# POSCON_PCB.net
KiCad netlist of a schematic drawn in EAGLE
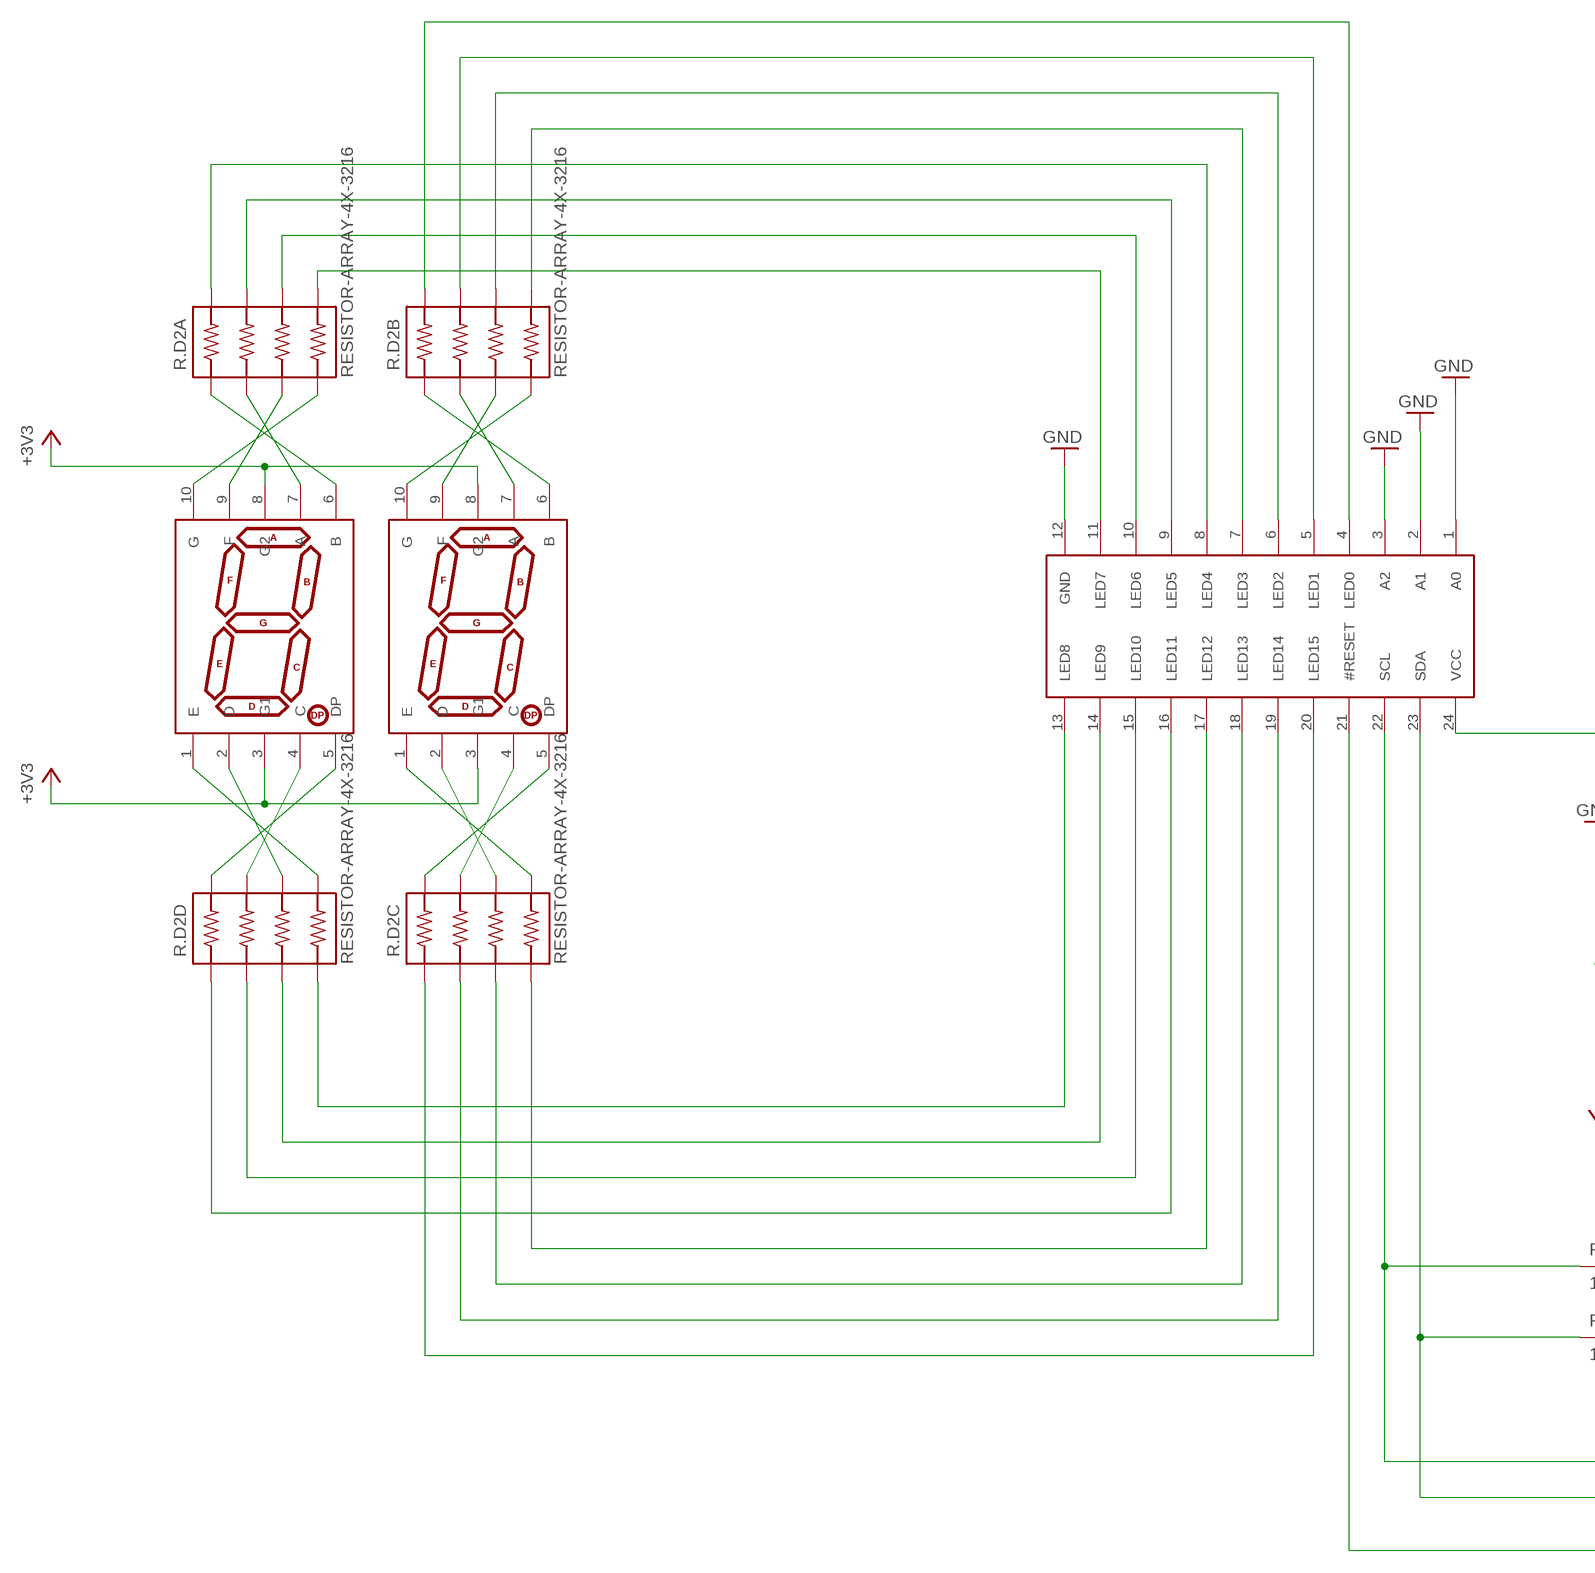
[diagram p0: schematic, sheet 1, part 1 of 2]
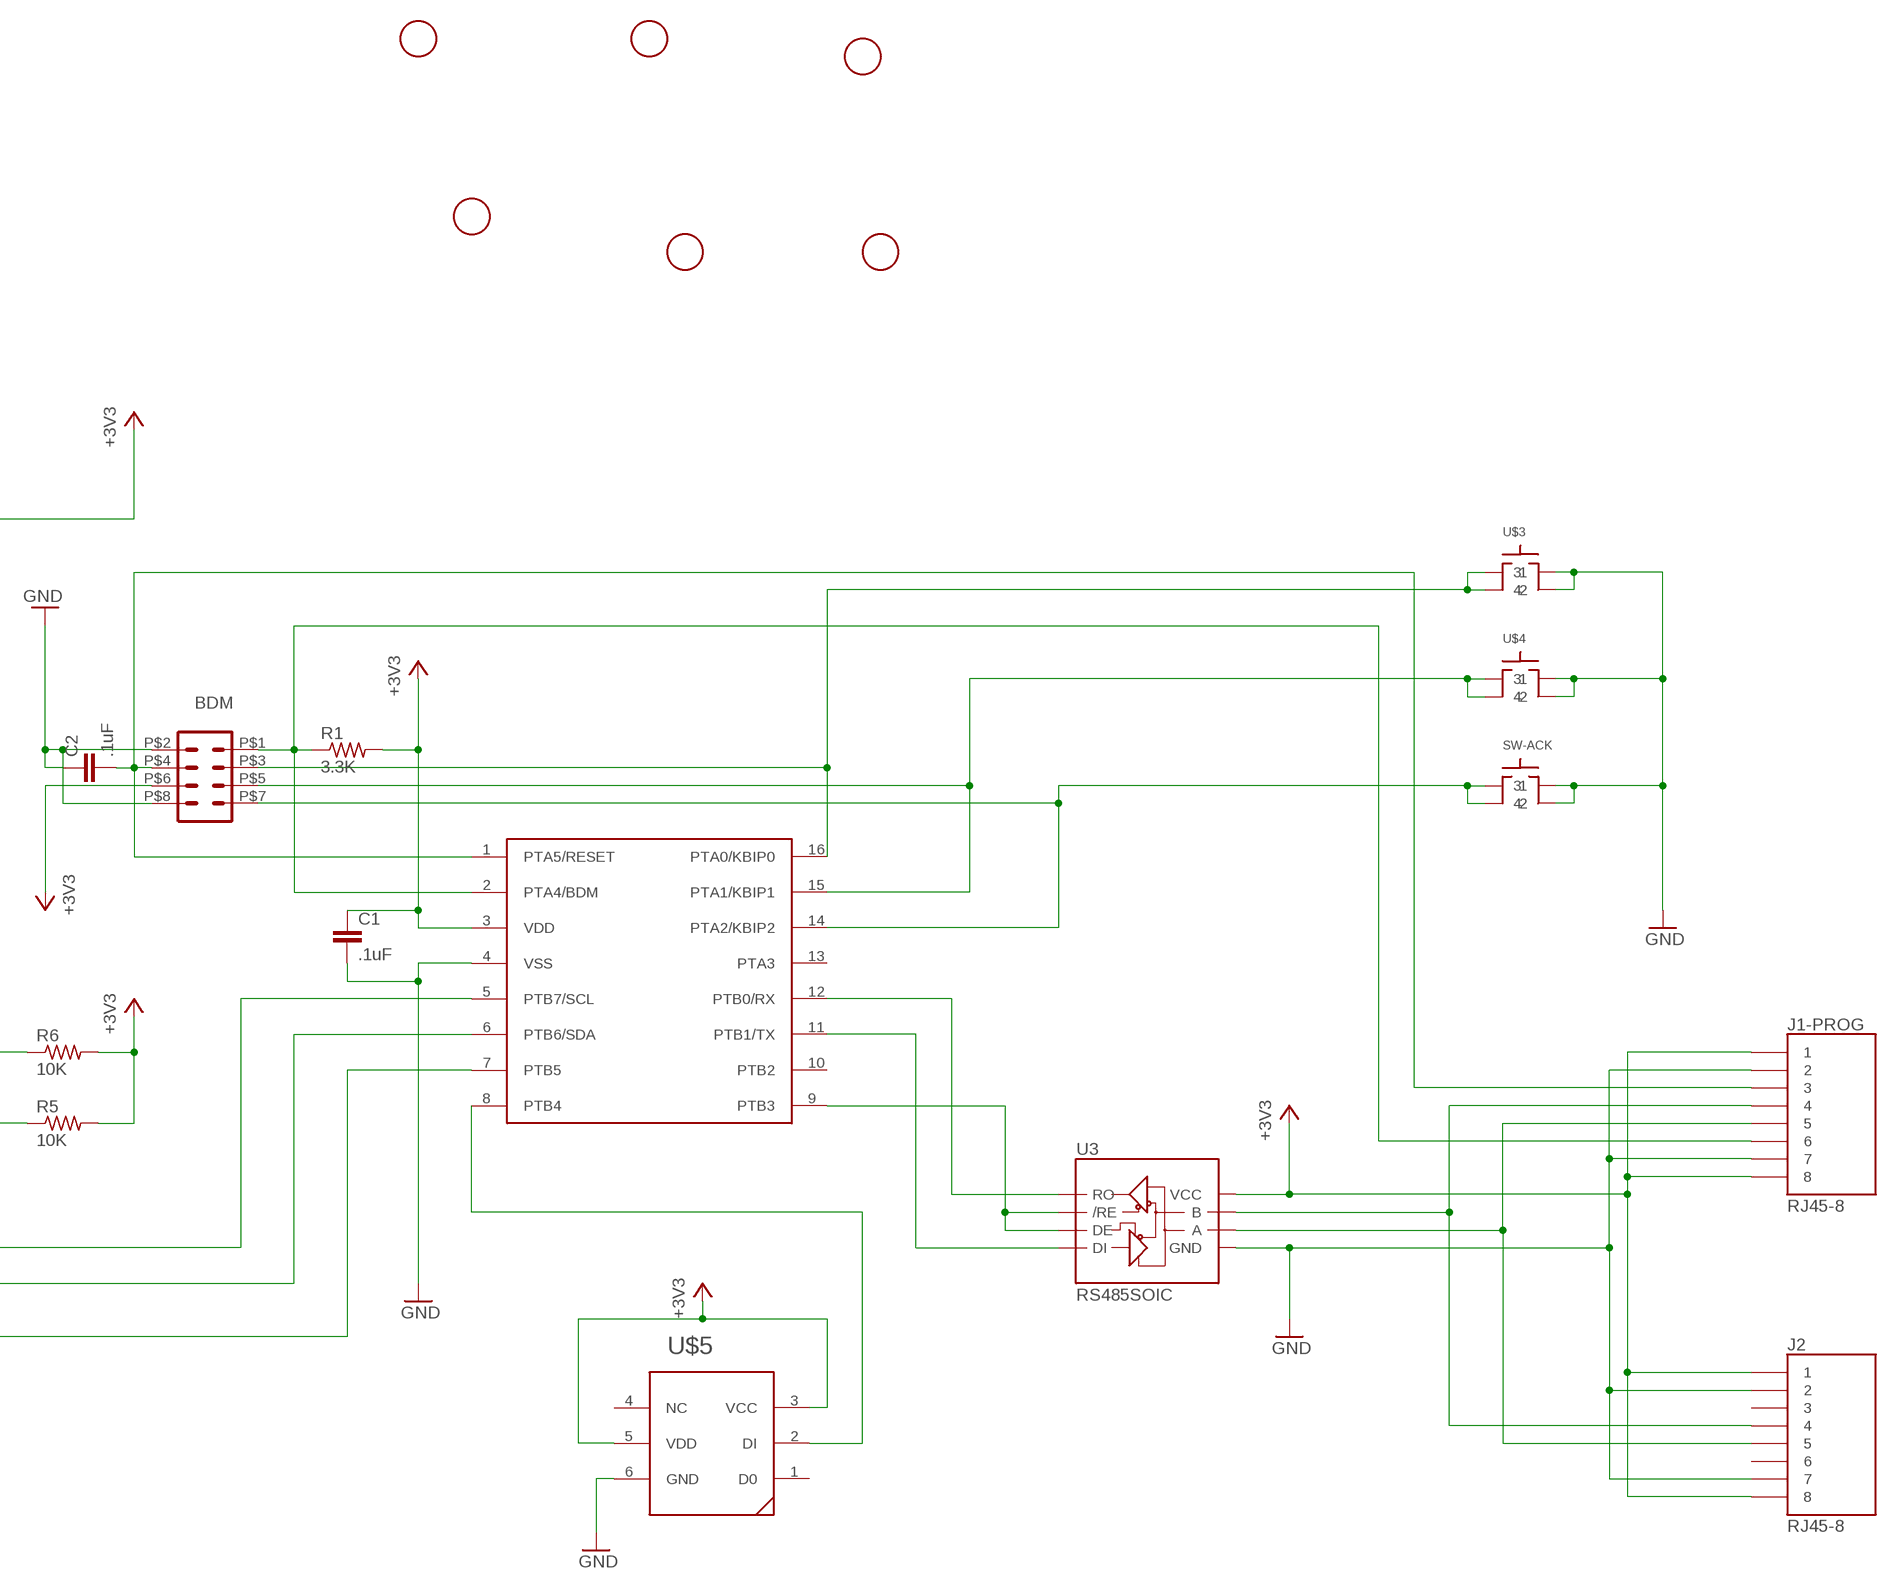
[diagram p1: schematic, sheet 1, part 2 of 2]

(export (version "E")
  (design (tool "Eeschema 10.0.6"))
  (components
    (comp (ref "BDM")
      (value "TP2X4SMD")
      (footprint "eagle-import:SMD4X2")
      (libsource (lib "eagle-import") (part "TP2X4SMD"))
    )
    (comp (ref "C1")
      (value ".1uF")
      (footprint "eagle-import:C0402")
      (libsource (lib "eagle-import") (part "RF-C0402"))
    )
    (comp (ref "C2")
      (value ".1uF")
      (footprint "eagle-import:C0402")
      (libsource (lib "eagle-import") (part "RF-C0402"))
    )
    (comp (ref "J1-PROG")
      (value "RJ45-8")
      (footprint "eagle-import:MOLEX-0955016649")
      (libsource (lib "eagle-import") (part "RJ45-8"))
    )
    (comp (ref "J2")
      (value "RJ45-8")
      (footprint "eagle-import:MOLEX-0955016649")
      (libsource (lib "eagle-import") (part "RJ45-8"))
    )
    (comp (ref "LED1")
      (value "7SEGMENT-1DIGITSMD")
      (footprint "eagle-import:7SEGMENT-1DIG-.40-SMD")
      (libsource (lib "eagle-import") (part "7SEGMENT-1DIGITSMD"))
    )
    (comp (ref "LED2")
      (value "7SEGMENT-1DIGITSMD")
      (footprint "eagle-import:7SEGMENT-1DIG-.40-SMD")
      (libsource (lib "eagle-import") (part "7SEGMENT-1DIGITSMD"))
    )
    (comp (ref "R.D2A")
      (value "RESISTOR-ARRAY-4X-3216")
      (footprint "eagle-import:3216-4X")
      (libsource (lib "eagle-import") (part "RESISTOR-ARRAY-4X-3216"))
    )
    (comp (ref "R.D2B")
      (value "RESISTOR-ARRAY-4X-3216")
      (footprint "eagle-import:3216-4X")
      (libsource (lib "eagle-import") (part "RESISTOR-ARRAY-4X-3216"))
    )
    (comp (ref "R.D2C")
      (value "RESISTOR-ARRAY-4X-3216")
      (footprint "eagle-import:3216-4X")
      (libsource (lib "eagle-import") (part "RESISTOR-ARRAY-4X-3216"))
    )
    (comp (ref "R.D2D")
      (value "RESISTOR-ARRAY-4X-3216")
      (footprint "eagle-import:3216-4X")
      (libsource (lib "eagle-import") (part "RESISTOR-ARRAY-4X-3216"))
    )
    (comp (ref "R1")
      (value "3.3K")
      (footprint "eagle-import:RF-R0402")
      (libsource (lib "eagle-import") (part "RF-R0402"))
    )
    (comp (ref "R5")
      (value "10K")
      (footprint "eagle-import:RF-R0402")
      (libsource (lib "eagle-import") (part "RF-R0402"))
    )
    (comp (ref "R6")
      (value "10K")
      (footprint "eagle-import:RF-R0402")
      (libsource (lib "eagle-import") (part "RF-R0402"))
    )
    (comp (ref "SW-ACK")
      (value "SWITCH-TACTILE-320.01E11WHT")
      (footprint "eagle-import:SWITCH-TACTILE-320.01E11WHT")
      (fields (field (name "MFGP") "320.01E11WHT"))
      (libsource (lib "eagle-import") (part "SWITCH-TACTILE-320.01E11WHT"))
    )
    (comp (ref "U$1")
      (value "FIDUCIAL")
      (footprint "eagle-import:FIDUCIAL_1MM")
      (libsource (lib "eagle-import") (part "FIDUCIAL"))
    )
    (comp (ref "U$2")
      (value "FIDUCIAL")
      (footprint "eagle-import:FIDUCIAL_1MM")
      (libsource (lib "eagle-import") (part "FIDUCIAL"))
    )
    (comp (ref "U$3")
      (value "SWITCH-TACTILE")
      (footprint "eagle-import:ESWITCH-TL3301PF")
      (libsource (lib "eagle-import") (part "SWITCH-TACTILE"))
    )
    (comp (ref "U$4")
      (value "SWITCH-TACTILE")
      (footprint "eagle-import:ESWITCH-TL3301PF")
      (libsource (lib "eagle-import") (part "SWITCH-TACTILE"))
    )
    (comp (ref "U$5")
      (value "WS2812")
      (footprint "eagle-import:PLCC-6")
      (libsource (lib "eagle-import") (part "WS2812"))
    )
    (comp (ref "U$6")
      (value "FIDUCIAL")
      (footprint "eagle-import:FIDUCIAL_1MM")
      (libsource (lib "eagle-import") (part "FIDUCIAL"))
    )
    (comp (ref "U$7")
      (value "FIDUCIAL")
      (footprint "eagle-import:FIDUCIAL_1MM")
      (libsource (lib "eagle-import") (part "FIDUCIAL"))
    )
    (comp (ref "U$8")
      (value "FIDUCIAL")
      (footprint "eagle-import:FIDUCIAL_1MM")
      (libsource (lib "eagle-import") (part "FIDUCIAL"))
    )
    (comp (ref "U$9")
      (value "FIDUCIAL")
      (footprint "eagle-import:FIDUCIAL_1MM")
      (libsource (lib "eagle-import") (part "FIDUCIAL"))
    )
    (comp (ref "U1")
      (value "MC9S08QG-DT")
      (footprint "eagle-import:TSSOP16")
      (libsource (lib "eagle-import") (part "MC9S08QG-DT"))
    )
    (comp (ref "U3")
      (value "RS485SOIC")
      (footprint "eagle-import:SO08")
      (libsource (lib "eagle-import") (part "RS485SOIC"))
    )
    (comp (ref "U4")
      (value "PCA9552")
      (footprint "eagle-import:TSSOP24")
      (fields (field (name "MFGP") "PCA9552PW,112"))
      (libsource (lib "eagle-import") (part "PCA9552"))
    )
  )
  (nets
    (net (code "1") (name "+3V3") (class "Default")
      (node (ref "BDM") (pin "P$6") (pinfunction "6_P$6") (pintype "passive"))
      (node (ref "C1") (pin "1") (pinfunction "1_1") (pintype "passive"))
      (node (ref "J1-PROG") (pin "P$1") (pinfunction "1_P$1") (pintype "bidirectional"))
      (node (ref "J1-PROG") (pin "P$8") (pinfunction "8_P$8") (pintype "bidirectional"))
      (node (ref "J2") (pin "P$1") (pinfunction "1_P$1") (pintype "bidirectional"))
      (node (ref "J2") (pin "P$8") (pinfunction "8_P$8") (pintype "bidirectional"))
      (node (ref "LED1") (pin "3") (pinfunction "G1_3") (pintype "bidirectional"))
      (node (ref "LED1") (pin "8") (pinfunction "G2_8") (pintype "bidirectional"))
      (node (ref "LED2") (pin "3") (pinfunction "G1_3") (pintype "bidirectional"))
      (node (ref "LED2") (pin "8") (pinfunction "G2_8") (pintype "bidirectional"))
      (node (ref "R1") (pin "2") (pinfunction "2_2") (pintype "passive"))
      (node (ref "R5") (pin "2") (pinfunction "2_2") (pintype "passive"))
      (node (ref "R6") (pin "2") (pinfunction "2_2") (pintype "passive"))
      (node (ref "U$5") (pin "3") (pinfunction "VCC_3") (pintype "bidirectional"))
      (node (ref "U$5") (pin "5") (pinfunction "VDD_5") (pintype "bidirectional"))
      (node (ref "U1") (pin "3") (pinfunction "VDD_3") (pintype "bidirectional"))
      (node (ref "U3") (pin "8") (pinfunction "VCC_8") (pintype "bidirectional"))
      (node (ref "U4") (pin "24") (pinfunction "VCC_24") (pintype "bidirectional"))
    )
    (net (code "2") (name "GND") (class "Default")
      (node (ref "BDM") (pin "P$2") (pinfunction "2_P$2") (pintype "passive"))
      (node (ref "BDM") (pin "P$8") (pinfunction "8_P$8") (pintype "passive"))
      (node (ref "C1") (pin "2") (pinfunction "2_2") (pintype "passive"))
      (node (ref "C2") (pin "1") (pinfunction "1_1") (pintype "passive"))
      (node (ref "J1-PROG") (pin "P$2") (pinfunction "2_P$2") (pintype "bidirectional"))
      (node (ref "J1-PROG") (pin "P$7") (pinfunction "7_P$7") (pintype "bidirectional"))
      (node (ref "J2") (pin "P$2") (pinfunction "2_P$2") (pintype "bidirectional"))
      (node (ref "J2") (pin "P$7") (pinfunction "7_P$7") (pintype "bidirectional"))
      (node (ref "SW-ACK") (pin "P$3") (pinfunction "3_P$3") (pintype "input"))
      (node (ref "SW-ACK") (pin "P$4") (pinfunction "4_P$4") (pintype "input"))
      (node (ref "U$3") (pin "3") (pinfunction "3_3") (pintype "input"))
      (node (ref "U$3") (pin "4") (pinfunction "4_4") (pintype "input"))
      (node (ref "U$4") (pin "3") (pinfunction "3_3") (pintype "input"))
      (node (ref "U$4") (pin "4") (pinfunction "4_4") (pintype "input"))
      (node (ref "U$5") (pin "6") (pinfunction "GND_6") (pintype "bidirectional"))
      (node (ref "U1") (pin "4") (pinfunction "VSS_4") (pintype "bidirectional"))
      (node (ref "U3") (pin "5") (pinfunction "GND_5") (pintype "bidirectional"))
      (node (ref "U4") (pin "1") (pinfunction "A0_1") (pintype "bidirectional"))
      (node (ref "U4") (pin "12") (pinfunction "GND_12") (pintype "bidirectional"))
      (node (ref "U4") (pin "2") (pinfunction "A1_2") (pintype "bidirectional"))
      (node (ref "U4") (pin "3") (pinfunction "A2_3") (pintype "bidirectional"))
    )
    (net (code "3") (name "Net-(BDM-1)") (class "Default")
      (node (ref "BDM") (pin "P$1") (pinfunction "1_P$1") (pintype "passive"))
      (node (ref "J1-PROG") (pin "P$6") (pinfunction "6_P$6") (pintype "bidirectional"))
      (node (ref "R1") (pin "1") (pinfunction "1_1") (pintype "passive"))
      (node (ref "U1") (pin "2") (pinfunction "PTA4/BDM_2") (pintype "bidirectional"))
    )
    (net (code "4") (name "Net-(BDM-3)") (class "Default")
      (node (ref "BDM") (pin "P$3") (pinfunction "3_P$3") (pintype "passive"))
      (node (ref "U$3") (pin "1") (pinfunction "1_1") (pintype "input"))
      (node (ref "U$3") (pin "2") (pinfunction "2_2") (pintype "input"))
      (node (ref "U1") (pin "16") (pinfunction "PTA0/KBIP0_16") (pintype "bidirectional"))
    )
    (net (code "5") (name "Net-(BDM-4)") (class "Default")
      (node (ref "BDM") (pin "P$4") (pinfunction "4_P$4") (pintype "passive"))
      (node (ref "C2") (pin "2") (pinfunction "2_2") (pintype "passive"))
      (node (ref "J1-PROG") (pin "P$3") (pinfunction "3_P$3") (pintype "bidirectional"))
      (node (ref "U1") (pin "1") (pinfunction "PTA5/RESET_1") (pintype "bidirectional"))
    )
    (net (code "6") (name "Net-(BDM-5)") (class "Default")
      (node (ref "BDM") (pin "P$5") (pinfunction "5_P$5") (pintype "passive"))
      (node (ref "U$4") (pin "1") (pinfunction "1_1") (pintype "input"))
      (node (ref "U$4") (pin "2") (pinfunction "2_2") (pintype "input"))
      (node (ref "U1") (pin "15") (pinfunction "PTA1/KBIP1_15") (pintype "bidirectional"))
    )
    (net (code "7") (name "Net-(BDM-7)") (class "Default")
      (node (ref "BDM") (pin "P$7") (pinfunction "7_P$7") (pintype "passive"))
      (node (ref "SW-ACK") (pin "P$1") (pinfunction "1_P$1") (pintype "input"))
      (node (ref "SW-ACK") (pin "P$2") (pinfunction "2_P$2") (pintype "input"))
      (node (ref "U1") (pin "14") (pinfunction "PTA2/KBIP2_14") (pintype "bidirectional"))
    )
    (net (code "8") (name "Net-(J1-PROG-4)") (class "Default")
      (node (ref "J1-PROG") (pin "P$4") (pinfunction "4_P$4") (pintype "bidirectional"))
      (node (ref "J2") (pin "P$4") (pinfunction "4_P$4") (pintype "bidirectional"))
      (node (ref "U3") (pin "7") (pinfunction "B_7") (pintype "bidirectional"))
    )
    (net (code "9") (name "Net-(J1-PROG-5)") (class "Default")
      (node (ref "J1-PROG") (pin "P$5") (pinfunction "5_P$5") (pintype "bidirectional"))
      (node (ref "J2") (pin "P$5") (pinfunction "5_P$5") (pintype "bidirectional"))
      (node (ref "U3") (pin "6") (pinfunction "A_6") (pintype "bidirectional"))
    )
    (net (code "10") (name "Net-(LED1-A)") (class "Default")
      (node (ref "LED1") (pin "7") (pinfunction "A_7") (pintype "bidirectional"))
      (node (ref "R.D2B") (pin "2") (pinfunction "2A_2") (pintype "passive"))
    )
    (net (code "11") (name "Net-(LED1-B)") (class "Default")
      (node (ref "LED1") (pin "6") (pinfunction "B_6") (pintype "bidirectional"))
      (node (ref "R.D2B") (pin "1") (pinfunction "1A_1") (pintype "passive"))
    )
    (net (code "12") (name "Net-(LED1-C)") (class "Default")
      (node (ref "LED1") (pin "4") (pinfunction "C_4") (pintype "bidirectional"))
      (node (ref "R.D2C") (pin "7") (pinfunction "2B_7") (pintype "passive"))
    )
    (net (code "13") (name "Net-(LED1-D)") (class "Default")
      (node (ref "LED1") (pin "2") (pinfunction "D_2") (pintype "bidirectional"))
      (node (ref "R.D2C") (pin "6") (pinfunction "3B_6") (pintype "passive"))
    )
    (net (code "14") (name "Net-(LED1-DP)") (class "Default")
      (node (ref "LED1") (pin "5") (pinfunction "DP_5") (pintype "bidirectional"))
      (node (ref "R.D2C") (pin "8") (pinfunction "1B_8") (pintype "passive"))
    )
    (net (code "15") (name "Net-(LED1-E)") (class "Default")
      (node (ref "LED1") (pin "1") (pinfunction "E_1") (pintype "bidirectional"))
      (node (ref "R.D2C") (pin "5") (pinfunction "4B_5") (pintype "passive"))
    )
    (net (code "16") (name "Net-(LED1-F)") (class "Default")
      (node (ref "LED1") (pin "9") (pinfunction "F_9") (pintype "bidirectional"))
      (node (ref "R.D2B") (pin "3") (pinfunction "3A_3") (pintype "passive"))
    )
    (net (code "17") (name "Net-(LED1-G)") (class "Default")
      (node (ref "LED1") (pin "10") (pinfunction "G_10") (pintype "bidirectional"))
      (node (ref "R.D2B") (pin "4") (pinfunction "4A_4") (pintype "passive"))
    )
    (net (code "18") (name "Net-(LED2-A)") (class "Default")
      (node (ref "LED2") (pin "7") (pinfunction "A_7") (pintype "bidirectional"))
      (node (ref "R.D2A") (pin "2") (pinfunction "2A_2") (pintype "passive"))
    )
    (net (code "19") (name "Net-(LED2-B)") (class "Default")
      (node (ref "LED2") (pin "6") (pinfunction "B_6") (pintype "bidirectional"))
      (node (ref "R.D2A") (pin "1") (pinfunction "1A_1") (pintype "passive"))
    )
    (net (code "20") (name "Net-(LED2-C)") (class "Default")
      (node (ref "LED2") (pin "4") (pinfunction "C_4") (pintype "bidirectional"))
      (node (ref "R.D2D") (pin "7") (pinfunction "2B_7") (pintype "passive"))
    )
    (net (code "21") (name "Net-(LED2-D)") (class "Default")
      (node (ref "LED2") (pin "2") (pinfunction "D_2") (pintype "bidirectional"))
      (node (ref "R.D2D") (pin "6") (pinfunction "3B_6") (pintype "passive"))
    )
    (net (code "22") (name "Net-(LED2-DP)") (class "Default")
      (node (ref "LED2") (pin "5") (pinfunction "DP_5") (pintype "bidirectional"))
      (node (ref "R.D2D") (pin "8") (pinfunction "1B_8") (pintype "passive"))
    )
    (net (code "23") (name "Net-(LED2-E)") (class "Default")
      (node (ref "LED2") (pin "1") (pinfunction "E_1") (pintype "bidirectional"))
      (node (ref "R.D2D") (pin "5") (pinfunction "4B_5") (pintype "passive"))
    )
    (net (code "24") (name "Net-(LED2-F)") (class "Default")
      (node (ref "LED2") (pin "9") (pinfunction "F_9") (pintype "bidirectional"))
      (node (ref "R.D2A") (pin "3") (pinfunction "3A_3") (pintype "passive"))
    )
    (net (code "25") (name "Net-(LED2-G)") (class "Default")
      (node (ref "LED2") (pin "10") (pinfunction "G_10") (pintype "bidirectional"))
      (node (ref "R.D2A") (pin "4") (pinfunction "4A_4") (pintype "passive"))
    )
    (net (code "26") (name "Net-(R.D2A-1B)") (class "Default")
      (node (ref "R.D2A") (pin "8") (pinfunction "1B_8") (pintype "passive"))
      (node (ref "U4") (pin "8") (pinfunction "LED4_8") (pintype "bidirectional"))
    )
    (net (code "27") (name "Net-(R.D2A-2B)") (class "Default")
      (node (ref "R.D2A") (pin "7") (pinfunction "2B_7") (pintype "passive"))
      (node (ref "U4") (pin "9") (pinfunction "LED5_9") (pintype "bidirectional"))
    )
    (net (code "28") (name "Net-(R.D2A-3B)") (class "Default")
      (node (ref "R.D2A") (pin "6") (pinfunction "3B_6") (pintype "passive"))
      (node (ref "U4") (pin "10") (pinfunction "LED6_10") (pintype "bidirectional"))
    )
    (net (code "29") (name "Net-(R.D2A-4B)") (class "Default")
      (node (ref "R.D2A") (pin "5") (pinfunction "4B_5") (pintype "passive"))
      (node (ref "U4") (pin "11") (pinfunction "LED7_11") (pintype "bidirectional"))
    )
    (net (code "30") (name "Net-(R.D2B-1B)") (class "Default")
      (node (ref "R.D2B") (pin "8") (pinfunction "1B_8") (pintype "passive"))
      (node (ref "U4") (pin "4") (pinfunction "LED0_4") (pintype "bidirectional"))
    )
    (net (code "31") (name "Net-(R.D2B-2B)") (class "Default")
      (node (ref "R.D2B") (pin "7") (pinfunction "2B_7") (pintype "passive"))
      (node (ref "U4") (pin "5") (pinfunction "LED1_5") (pintype "bidirectional"))
    )
    (net (code "32") (name "Net-(R.D2B-3B)") (class "Default")
      (node (ref "R.D2B") (pin "6") (pinfunction "3B_6") (pintype "passive"))
      (node (ref "U4") (pin "6") (pinfunction "LED2_6") (pintype "bidirectional"))
    )
    (net (code "33") (name "Net-(R.D2B-4B)") (class "Default")
      (node (ref "R.D2B") (pin "5") (pinfunction "4B_5") (pintype "passive"))
      (node (ref "U4") (pin "7") (pinfunction "LED3_7") (pintype "bidirectional"))
    )
    (net (code "34") (name "Net-(R.D2C-1A)") (class "Default")
      (node (ref "R.D2C") (pin "1") (pinfunction "1A_1") (pintype "passive"))
      (node (ref "U4") (pin "20") (pinfunction "LED15_20") (pintype "bidirectional"))
    )
    (net (code "35") (name "Net-(R.D2C-2A)") (class "Default")
      (node (ref "R.D2C") (pin "2") (pinfunction "2A_2") (pintype "passive"))
      (node (ref "U4") (pin "19") (pinfunction "LED14_19") (pintype "bidirectional"))
    )
    (net (code "36") (name "Net-(R.D2C-3A)") (class "Default")
      (node (ref "R.D2C") (pin "3") (pinfunction "3A_3") (pintype "passive"))
      (node (ref "U4") (pin "18") (pinfunction "LED13_18") (pintype "bidirectional"))
    )
    (net (code "37") (name "Net-(R.D2C-4A)") (class "Default")
      (node (ref "R.D2C") (pin "4") (pinfunction "4A_4") (pintype "passive"))
      (node (ref "U4") (pin "17") (pinfunction "LED12_17") (pintype "bidirectional"))
    )
    (net (code "38") (name "Net-(R.D2D-1A)") (class "Default")
      (node (ref "R.D2D") (pin "1") (pinfunction "1A_1") (pintype "passive"))
      (node (ref "U4") (pin "16") (pinfunction "LED11_16") (pintype "bidirectional"))
    )
    (net (code "39") (name "Net-(R.D2D-2A)") (class "Default")
      (node (ref "R.D2D") (pin "2") (pinfunction "2A_2") (pintype "passive"))
      (node (ref "U4") (pin "15") (pinfunction "LED10_15") (pintype "bidirectional"))
    )
    (net (code "40") (name "Net-(R.D2D-3A)") (class "Default")
      (node (ref "R.D2D") (pin "3") (pinfunction "3A_3") (pintype "passive"))
      (node (ref "U4") (pin "14") (pinfunction "LED9_14") (pintype "bidirectional"))
    )
    (net (code "41") (name "Net-(R.D2D-4A)") (class "Default")
      (node (ref "R.D2D") (pin "4") (pinfunction "4A_4") (pintype "passive"))
      (node (ref "U4") (pin "13") (pinfunction "LED8_13") (pintype "bidirectional"))
    )
    (net (code "42") (name "Net-(U$5-DI)") (class "Default")
      (node (ref "U$5") (pin "2") (pinfunction "DI_2") (pintype "bidirectional"))
      (node (ref "U1") (pin "8") (pinfunction "PTB4_8") (pintype "bidirectional"))
    )
    (net (code "43") (name "Net-(U1-PTB0{slash}RX)") (class "Default")
      (node (ref "U1") (pin "12") (pinfunction "PTB0/RX_12") (pintype "bidirectional"))
      (node (ref "U3") (pin "1") (pinfunction "RO_1") (pintype "bidirectional"))
    )
    (net (code "44") (name "Net-(U1-PTB1{slash}TX)") (class "Default")
      (node (ref "U1") (pin "11") (pinfunction "PTB1/TX_11") (pintype "bidirectional"))
      (node (ref "U3") (pin "4") (pinfunction "DI_4") (pintype "bidirectional"))
    )
    (net (code "45") (name "Net-(U1-PTB3)") (class "Default")
      (node (ref "U1") (pin "9") (pinfunction "PTB3_9") (pintype "bidirectional"))
      (node (ref "U3") (pin "2") (pinfunction "/RE_2") (pintype "bidirectional"))
      (node (ref "U3") (pin "3") (pinfunction "DE_3") (pintype "bidirectional"))
    )
    (net (code "46") (name "Net-(U1-PTB5)") (class "Default")
      (node (ref "U1") (pin "7") (pinfunction "PTB5_7") (pintype "bidirectional"))
      (node (ref "U4") (pin "21") (pinfunction "#RESET_21") (pintype "bidirectional"))
    )
    (net (code "47") (name "Net-(U1-PTB6{slash}SDA)") (class "Default")
      (node (ref "R5") (pin "1") (pinfunction "1_1") (pintype "passive"))
      (node (ref "U1") (pin "6") (pinfunction "PTB6/SDA_6") (pintype "bidirectional"))
      (node (ref "U4") (pin "23") (pinfunction "SDA_23") (pintype "bidirectional"))
    )
    (net (code "48") (name "Net-(U1-PTB7{slash}SCL)") (class "Default")
      (node (ref "R6") (pin "1") (pinfunction "1_1") (pintype "passive"))
      (node (ref "U1") (pin "5") (pinfunction "PTB7/SCL_5") (pintype "bidirectional"))
      (node (ref "U4") (pin "22") (pinfunction "SCL_22") (pintype "bidirectional"))
    )
    (net (code "49") (name "unconnected-(J2-3-PadP$3)") (class "Default")
      (node (ref "J2") (pin "P$3") (pinfunction "3_P$3") (pintype "bidirectional"))
    )
    (net (code "50") (name "unconnected-(J2-6-PadP$6)") (class "Default")
      (node (ref "J2") (pin "P$6") (pinfunction "6_P$6") (pintype "bidirectional"))
    )
    (net (code "51") (name "unconnected-(U$5-D0-Pad1)") (class "Default")
      (node (ref "U$5") (pin "1") (pinfunction "D0_1") (pintype "bidirectional"))
    )
    (net (code "52") (name "unconnected-(U$5-NC-Pad4)") (class "Default")
      (node (ref "U$5") (pin "4") (pinfunction "NC_4") (pintype "bidirectional"))
    )
    (net (code "53") (name "unconnected-(U1-PTA3-Pad13)") (class "Default")
      (node (ref "U1") (pin "13") (pinfunction "PTA3_13") (pintype "bidirectional"))
    )
    (net (code "54") (name "unconnected-(U1-PTB2-Pad10)") (class "Default")
      (node (ref "U1") (pin "10") (pinfunction "PTB2_10") (pintype "bidirectional"))
    )
  )
)
